# Cording.net
KiCad netlist of a schematic drawn in Altium Designer
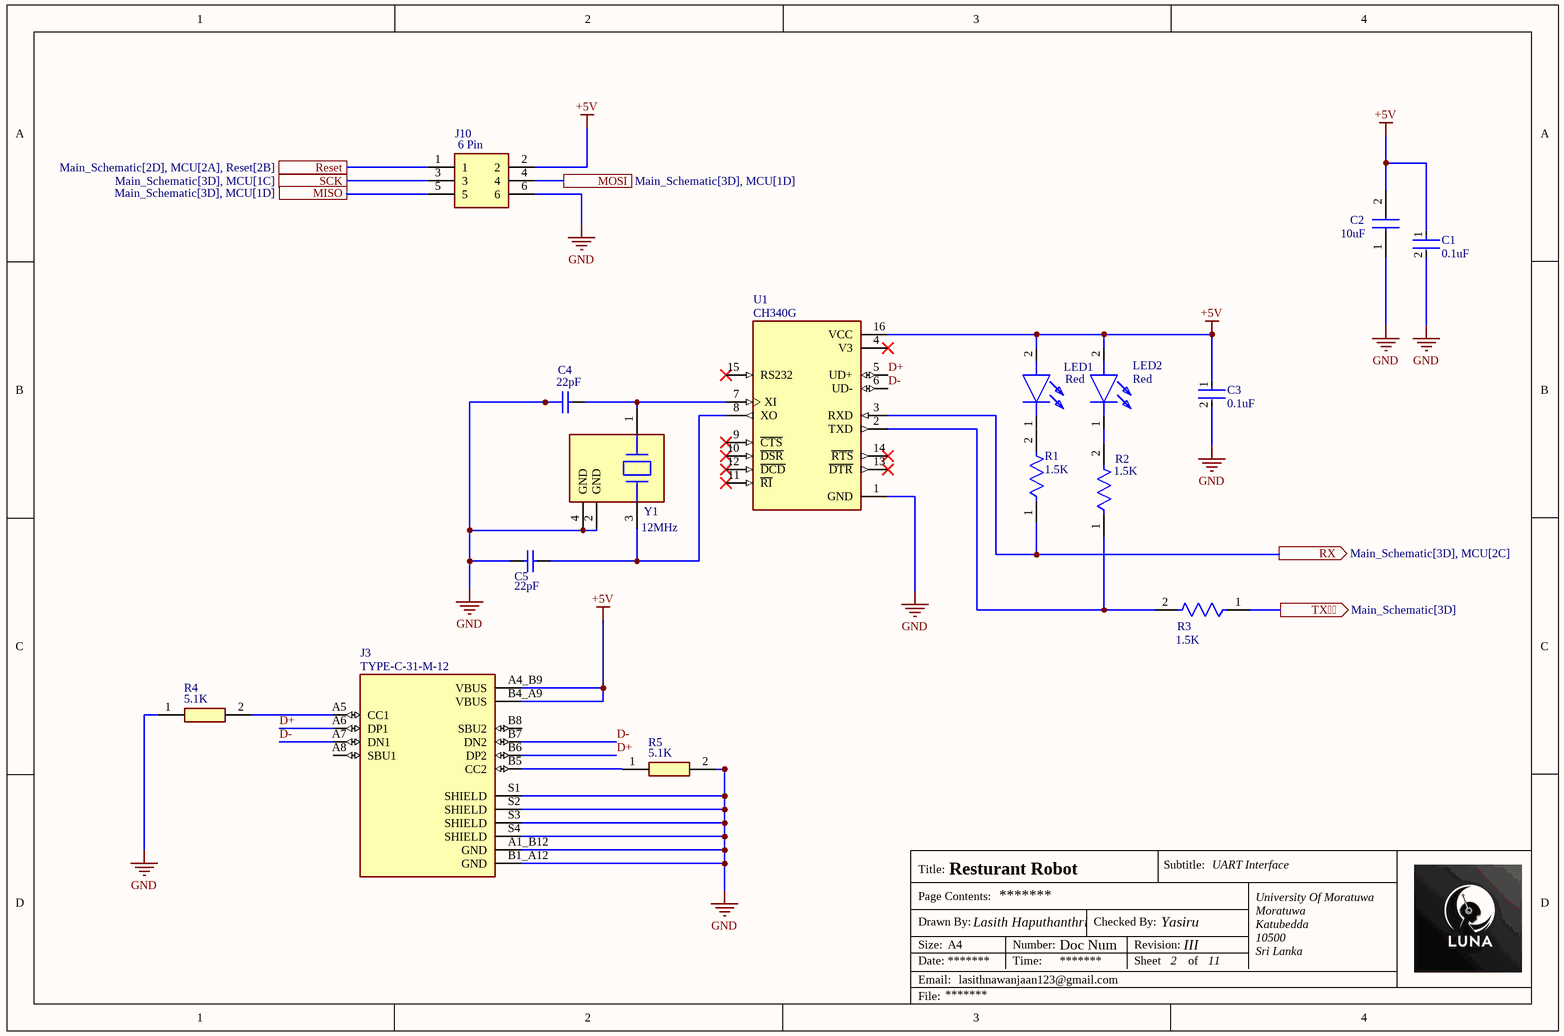
[diagram p0: Cording.SchDoc]

(export (version "E")
  (design (tool "Eeschema 10.0.6"))
  (components
    (comp (ref "C1")
      (value "0.1uF")
      (footprint "FP-CC0603-DA-MFG")
      (description "CC0603KRX7R9BB104 CAP CER 0.1UF 50V X7R 0603")
      (fields (field (name "MANUFACTURER") "YAGEO") (field (name "VOLTAGE") "50 V"))
      (libsource (lib "Altium Content Vault") (part "11868f565c42a9108669ba33697ecf6"))
    )
    (comp (ref "C2")
      (value "10uF")
      (footprint "SamacSys:CAPC1608X90N")
      (description "CL10A106KP8NNNC Capacitor")
      (fields
        (field (name "MANUFACTURER_PART_NUMBER") "CL10A106KP8NNNC")
        (field (name "MOUSER PART NUMBER") "187-CL10A106KP8NNNC")
      )
      (libsource (lib "*") (part "CL10A106KP8NNNC"))
    )
    (comp (ref "C3")
      (value "0.1uF")
      (footprint "FP-CC0603-DA-MFG")
      (description "CC0603KRX7R9BB104 CAP CER 0.1UF 50V X7R 0603")
      (fields (field (name "MANUFACTURER") "YAGEO") (field (name "VOLTAGE") "50 V"))
      (libsource (lib "Altium Content Vault") (part "11868f565c42a9108669ba33697ecf6"))
    )
    (comp (ref "C4")
      (value "22pF")
      (footprint "CAPC1608X90X40LL10T20")
      (libsource (lib "Altium Content Vault") (part "CAP-NP-2"))
    )
    (comp (ref "C5")
      (value "22pF")
      (footprint "CAPC1608X90X40LL10T20")
      (libsource (lib "Altium Content Vault") (part "CAP-NP-2"))
    )
    (comp (ref "J3")
      (value "TYPE-C-31-M-12")
      (footprint "HRO_TYPE-C-31-M-12")
      (description "USB Connectors 24 Receptacle 1 8.94*7.3mm RoHS")
      (fields (field (name "MF") "HRO Electronics Co., Ltd."))
      (libsource (lib "TYPE-C-31-M-12") (part "TYPE-C-31-M-12"))
    )
    (comp (ref "J10")
      (value "6 Pin")
      (footprint "SamacSys:HDRV6W64P254_2X3_762X508X868P")
      (description "Connector")
      (fields
        (field (name "MANUFACTURER_PART_NUMBER") "M20-9980346")
        (field (name "MOUSER PART NUMBER") "855-M20-9980346")
      )
      (libsource (lib "*") (part "M20-9980346"))
    )
    (comp (ref "LED1")
      (value "Red")
      (footprint "SamacSys:LEDC1608X55N")
      (description "LED")
      (fields
        (field (name "MANUFACTURER_PART_NUMBER") "LTST-C191KRKT")
        (field (name "MOUSER PART NUMBER") "859-LTST-C191KRKT")
      )
      (libsource (lib "*") (part "LTST-C191KRKT"))
    )
    (comp (ref "LED2")
      (value "Red")
      (footprint "SamacSys:LEDC1608X55N")
      (description "LED")
      (fields
        (field (name "MANUFACTURER_PART_NUMBER") "LTST-C191KRKT")
        (field (name "MOUSER PART NUMBER") "859-LTST-C191KRKT")
      )
      (libsource (lib "*") (part "LTST-C191KRKT"))
    )
    (comp (ref "R1")
      (value "1.5K")
      (footprint "FP-AF0603-IPC_B")
      (description "AF0603FR-071K5L Anti-Sulfurated Chip Resistors Automotive Grade 1.5kΩ 1% 100ppm/°C 0603")
      (fields (field (name "TOLERANCE") "1%"))
      (libsource (lib "Altium Content Vault") (part "1029c3af85768c4190bb7ad29bc67b5"))
    )
    (comp (ref "R2")
      (value "1.5K")
      (footprint "FP-AF0603-IPC_B")
      (description "AF0603FR-071K5L Anti-Sulfurated Chip Resistors Automotive Grade 1.5kΩ 1% 100ppm/°C 0603")
      (fields (field (name "TOLERANCE") "1%"))
      (libsource (lib "Altium Content Vault") (part "1029c3af85768c4190bb7ad29bc67b5"))
    )
    (comp (ref "R3")
      (value "1.5K")
      (footprint "FP-AF0603-IPC_B")
      (description "AF0603FR-071K5L Anti-Sulfurated Chip Resistors Automotive Grade 1.5kΩ 1% 100ppm/°C 0603")
      (fields (field (name "TOLERANCE") "1%"))
      (libsource (lib "Altium Content Vault") (part "1029c3af85768c4190bb7ad29bc67b5"))
    )
    (comp (ref "R4")
      (value "5.1K")
      (footprint "SamacSys:RESC1608X55N")
      (description "0603WAF5101T5E Resistor")
      (fields (field (name "MANUFACTURER_PART_NUMBER") "0603WAF5101T5E"))
      (libsource (lib "*") (part "0603WAF5101T5E"))
    )
    (comp (ref "R5")
      (value "5.1K")
      (footprint "SamacSys:RESC1608X55N")
      (description "0603WAF5101T5EResistor")
      (fields (field (name "MANUFACTURER_PART_NUMBER") "0603WAF5101T5E"))
      (libsource (lib "*") (part "0603WAF5101T5E"))
    )
    (comp (ref "U1")
      (value "CH340G")
      (footprint "SOIC127P600X180-16N")
      (description "USB Interface Integrated Circuit")
      (fields (field (name "MP") "Ch340G") (field (name "MF") "WCH"))
      (libsource (lib "CH340G") (part "CH340G"))
    )
    (comp (ref "Y1")
      (value "12MHz")
      (footprint "FP-ABM8G-MFG")
      (fields (field (name "TOLERANCE") "20ppm"))
      (libsource (lib "Altium Content Vault") (part "48e526d86b7f2615d98721063c72f49"))
    )
  )
  (nets
    (net (code "1") (name "+5V") (class "Default")
      (node (ref "C1") (pin "1") (pinfunction "1_1") (pintype "passive"))
      (node (ref "C2") (pin "2") (pinfunction "2_2") (pintype "passive"))
      (node (ref "C3") (pin "1") (pinfunction "1_1") (pintype "passive"))
      (node (ref "J10") (pin "2") (pinfunction "2_2") (pintype "passive"))
      (node (ref "J3") (pin "A4_B9") (pinfunction "VBUS_A4_B9") (pintype "power_in"))
      (node (ref "J3") (pin "B4_A9") (pinfunction "VBUS_B4_A9") (pintype "power_in"))
      (node (ref "LED1") (pin "2") (pinfunction "A_2") (pintype "passive"))
      (node (ref "LED2") (pin "2") (pinfunction "A_2") (pintype "passive"))
      (node (ref "U1") (pin "16") (pinfunction "VCC_16") (pintype "power_in"))
    )
    (net (code "2") (name "/D+") (class "Default")
      (node (ref "J3") (pin "A6") (pinfunction "DP1_A6") (pintype "bidirectional"))
      (node (ref "J3") (pin "B6") (pinfunction "DP2_B6") (pintype "bidirectional"))
      (node (ref "U1") (pin "5") (pinfunction "UD+_5") (pintype "bidirectional"))
    )
    (net (code "3") (name "/D-") (class "Default")
      (node (ref "J3") (pin "A7") (pinfunction "DN1_A7") (pintype "bidirectional"))
      (node (ref "J3") (pin "B7") (pinfunction "DN2_B7") (pintype "bidirectional"))
      (node (ref "U1") (pin "6") (pinfunction "UD-_6") (pintype "bidirectional"))
    )
    (net (code "4") (name "/MISO") (class "Default")
      (node (ref "J10") (pin "5") (pinfunction "5_5") (pintype "passive"))
    )
    (net (code "5") (name "/MOSI") (class "Default")
      (node (ref "J10") (pin "4") (pinfunction "4_4") (pintype "passive"))
    )
    (net (code "6") (name "/RX") (class "Default")
      (node (ref "R1") (pin "1") (pinfunction "1_1") (pintype "passive"))
      (node (ref "U1") (pin "3") (pinfunction "RXD_3") (pintype "input"))
    )
    (net (code "7") (name "/Reset") (class "Default")
      (node (ref "J10") (pin "1") (pinfunction "1_1") (pintype "passive"))
    )
    (net (code "8") (name "/SCK") (class "Default")
      (node (ref "J10") (pin "3") (pinfunction "3_3") (pintype "passive"))
    )
    (net (code "9") (name "/TX") (class "Default")
      (node (ref "R3") (pin "1") (pinfunction "1_1") (pintype "passive"))
    )
    (net (code "10") (name "GND") (class "Default")
      (node (ref "C1") (pin "2") (pinfunction "2_2") (pintype "passive"))
      (node (ref "C2") (pin "1") (pinfunction "1_1") (pintype "passive"))
      (node (ref "C3") (pin "2") (pinfunction "2_2") (pintype "passive"))
      (node (ref "C4") (pin "1") (pinfunction "1_1") (pintype "passive"))
      (node (ref "C5") (pin "1") (pinfunction "1_1") (pintype "passive"))
      (node (ref "J10") (pin "6") (pinfunction "6_6") (pintype "passive"))
      (node (ref "J3") (pin "A1_B12") (pinfunction "GND_A1_B12") (pintype "power_in"))
      (node (ref "J3") (pin "B1_A12") (pinfunction "GND_B1_A12") (pintype "power_in"))
      (node (ref "J3") (pin "S1") (pinfunction "SHIELD_S1") (pintype "passive"))
      (node (ref "J3") (pin "S2") (pinfunction "SHIELD_S2") (pintype "passive"))
      (node (ref "J3") (pin "S3") (pinfunction "SHIELD_S3") (pintype "passive"))
      (node (ref "J3") (pin "S4") (pinfunction "SHIELD_S4") (pintype "passive"))
      (node (ref "R4") (pin "1") (pinfunction "1_1") (pintype "passive"))
      (node (ref "R5") (pin "2") (pinfunction "2_2") (pintype "passive"))
      (node (ref "U1") (pin "1") (pinfunction "GND_1") (pintype "power_in"))
      (node (ref "Y1") (pin "2") (pinfunction "GND_2") (pintype "power_in"))
      (node (ref "Y1") (pin "4") (pinfunction "GND_4") (pintype "power_in"))
    )
    (net (code "11") (name "Net-(J3-CC1)") (class "Default")
      (node (ref "J3") (pin "A5") (pinfunction "CC1_A5") (pintype "bidirectional"))
      (node (ref "R4") (pin "2") (pinfunction "2_2") (pintype "passive"))
    )
    (net (code "12") (name "Net-(J3-CC2)") (class "Default")
      (node (ref "J3") (pin "B5") (pinfunction "CC2_B5") (pintype "bidirectional"))
      (node (ref "R5") (pin "1") (pinfunction "1_1") (pintype "passive"))
    )
    (net (code "13") (name "Net-(LED1-K)") (class "Default")
      (node (ref "LED1") (pin "1") (pinfunction "K_1") (pintype "passive"))
      (node (ref "R1") (pin "2") (pinfunction "2_2") (pintype "passive"))
    )
    (net (code "14") (name "Net-(LED2-K)") (class "Default")
      (node (ref "LED2") (pin "1") (pinfunction "K_1") (pintype "passive"))
      (node (ref "R2") (pin "2") (pinfunction "2_2") (pintype "passive"))
    )
    (net (code "15") (name "Net-(U1-TXD)") (class "Default")
      (node (ref "R2") (pin "1") (pinfunction "1_1") (pintype "passive"))
      (node (ref "R3") (pin "2") (pinfunction "2_2") (pintype "passive"))
      (node (ref "U1") (pin "2") (pinfunction "TXD_2") (pintype "output"))
    )
    (net (code "16") (name "Net-(U1-XI)") (class "Default")
      (node (ref "C4") (pin "2") (pinfunction "2_2") (pintype "passive"))
      (node (ref "U1") (pin "7") (pinfunction "XI_7") (pintype "input"))
      (node (ref "Y1") (pin "1") (pinfunction "1_1") (pintype "passive"))
    )
    (net (code "17") (name "Net-(U1-XO)") (class "Default")
      (node (ref "C5") (pin "2") (pinfunction "2_2") (pintype "passive"))
      (node (ref "U1") (pin "8") (pinfunction "XO_8") (pintype "output"))
      (node (ref "Y1") (pin "3") (pinfunction "3_3") (pintype "passive"))
    )
    (net (code "18") (name "unconnected-(J3-SBU1-PadA8)") (class "Default")
      (node (ref "J3") (pin "A8") (pinfunction "SBU1_A8") (pintype "bidirectional"))
    )
    (net (code "19") (name "unconnected-(J3-SBU2-PadB8)") (class "Default")
      (node (ref "J3") (pin "B8") (pinfunction "SBU2_B8") (pintype "bidirectional"))
    )
    (net (code "20") (name "unconnected-(U1-RS232-Pad15)") (class "Default")
      (node (ref "U1") (pin "15") (pinfunction "RS232_15") (pintype "input+no_connect"))
    )
    (net (code "21") (name "unconnected-(U1-V3-Pad4)") (class "Default")
      (node (ref "U1") (pin "4") (pinfunction "V3_4") (pintype "power_in+no_connect"))
    )
    (net (code "22") (name "unconnected-(U1-~{CTS}-Pad9)") (class "Default")
      (node (ref "U1") (pin "9") (pinfunction "~{CTS}_9") (pintype "input+no_connect"))
    )
    (net (code "23") (name "unconnected-(U1-~{DCD}-Pad12)") (class "Default")
      (node (ref "U1") (pin "12") (pinfunction "~{DCD}_12") (pintype "input+no_connect"))
    )
    (net (code "24") (name "unconnected-(U1-~{DSR}-Pad10)") (class "Default")
      (node (ref "U1") (pin "10") (pinfunction "~{DSR}_10") (pintype "input+no_connect"))
    )
    (net (code "25") (name "unconnected-(U1-~{DTR}-Pad13)") (class "Default")
      (node (ref "U1") (pin "13") (pinfunction "~{DTR}_13") (pintype "output+no_connect"))
    )
    (net (code "26") (name "unconnected-(U1-~{RI}-Pad11)") (class "Default")
      (node (ref "U1") (pin "11") (pinfunction "~{RI}_11") (pintype "input+no_connect"))
    )
    (net (code "27") (name "unconnected-(U1-~{RTS}-Pad14)") (class "Default")
      (node (ref "U1") (pin "14") (pinfunction "~{RTS}_14") (pintype "output+no_connect"))
    )
  )
)
